# untitled.net
KiCad netlist of a schematic drawn in EAGLE
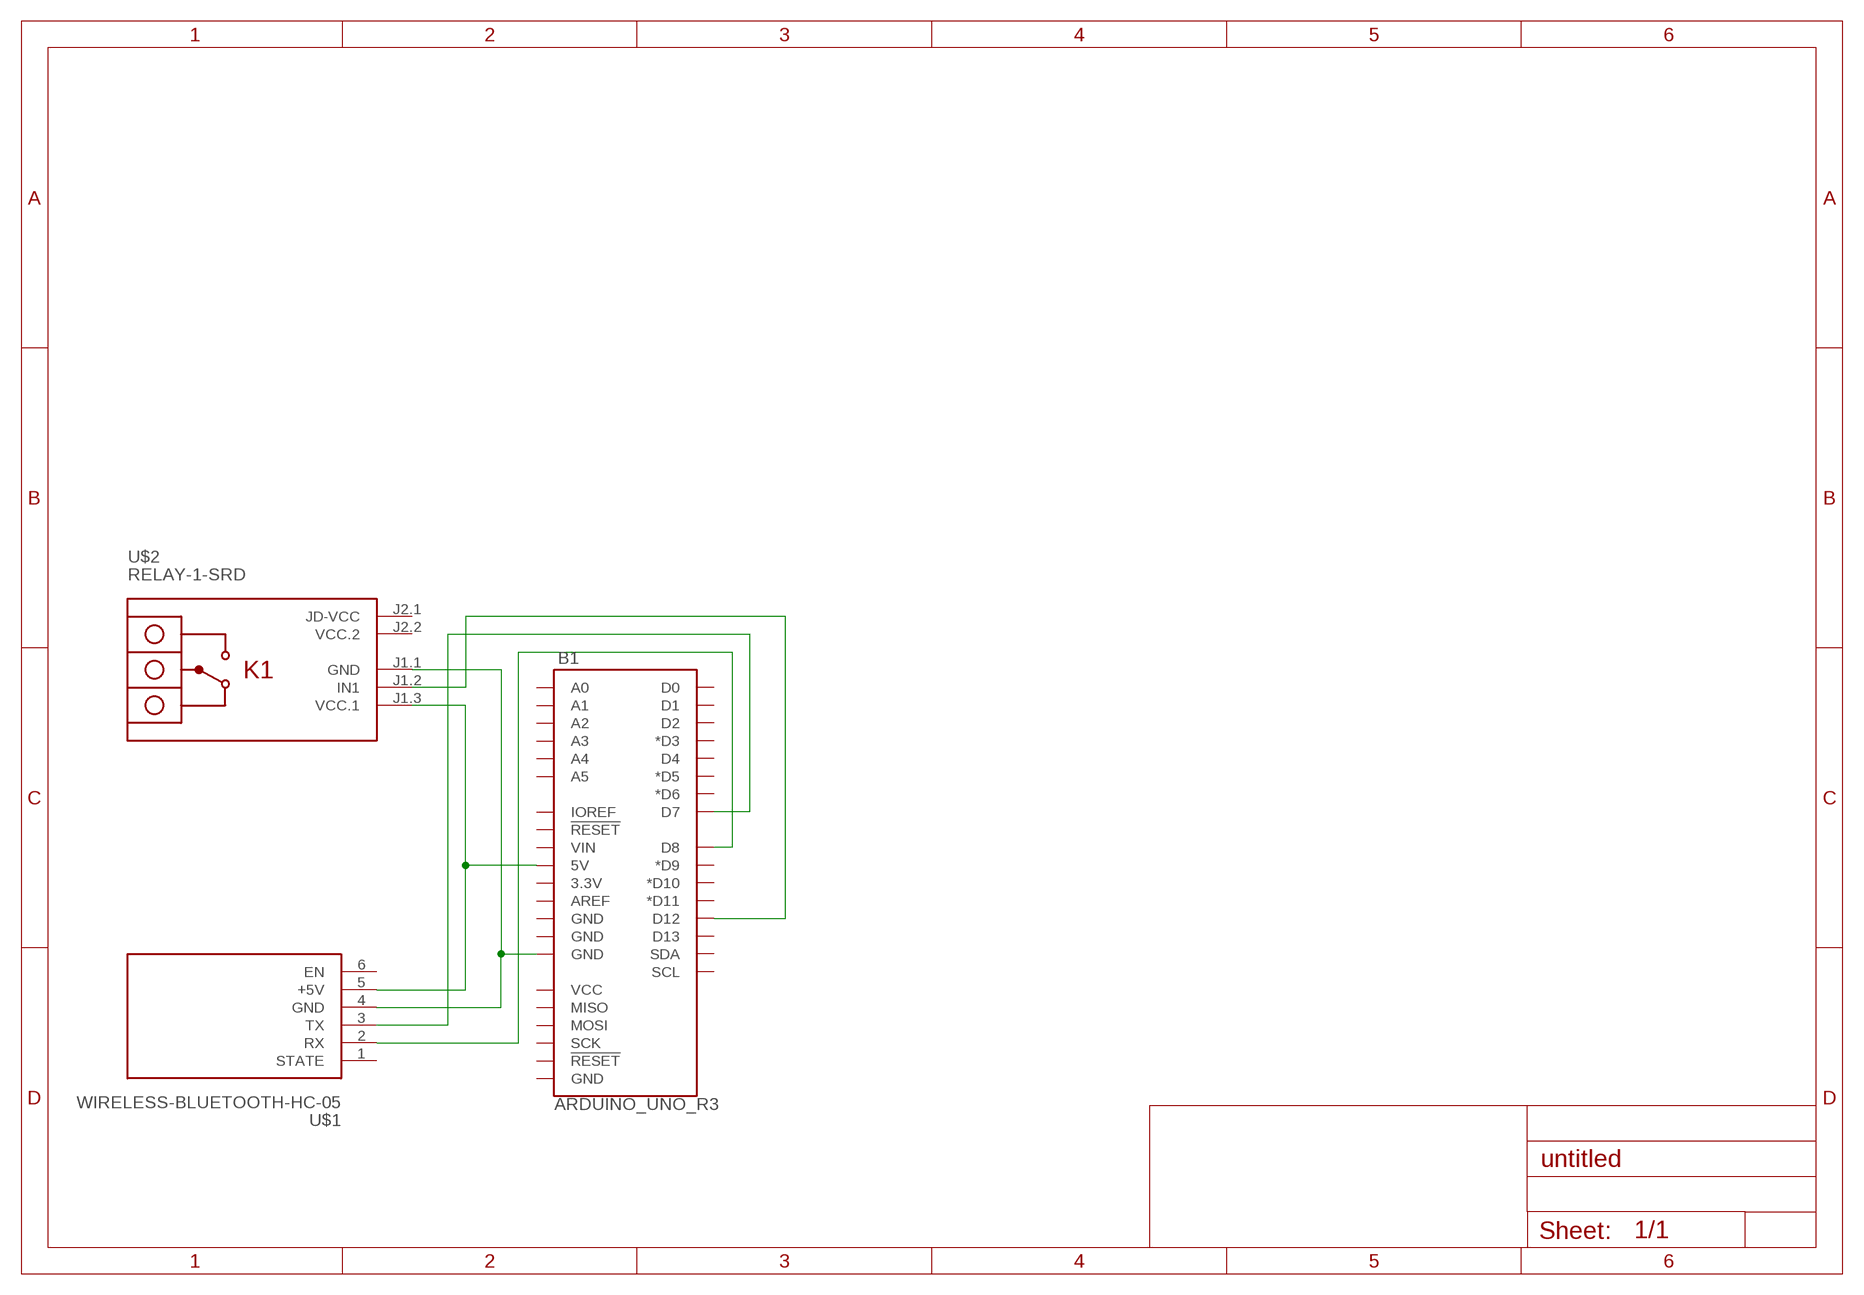
[diagram p0: schematic, sheet 1]

(export (version "E")
  (design (tool "Eeschema 10.0.6"))
  (components
    (comp (ref "B1")
      (value "ARDUINO_UNO_R3")
      (footprint "eagle-import:ARDUINO_R3")
      (libsource (lib "eagle-import") (part "ARDUINO_UNO_R3"))
    )
    (comp (ref "U$1")
      (value "WIRELESS-BLUETOOTH-HC-05")
      (footprint "eagle-import:WIRELESS-BLUETOOTH-HC-05")
      (libsource (lib "eagle-import") (part "WIRELESS-BLUETOOTH-HC-05"))
    )
    (comp (ref "U$2")
      (value "RELAY-1-SRD")
      (footprint "eagle-import:RELAY-1-SRD")
      (libsource (lib "eagle-import") (part "RELAY-1-SRD"))
    )
  )
  (nets
    (net (code "1") (name "/VCC.2") (class "Default")
      (node (ref "U$2") (pin "J2.2") (pinfunction "VCC.2_J2.2") (pintype "power_in"))
    )
    (net (code "2") (name "Net-(U$1-+5V)") (class "Default")
      (node (ref "B1") (pin "5V") (pinfunction "5V_5V") (pintype "bidirectional"))
      (node (ref "U$1") (pin "5") (pinfunction "+5V_5") (pintype "power_in"))
      (node (ref "U$2") (pin "J1.3") (pinfunction "VCC.1_J1.3") (pintype "power_in"))
    )
    (net (code "3") (name "Net-(U$1-GND)") (class "Default")
      (node (ref "B1") (pin "GND@2") (pinfunction "GND_GND@2") (pintype "bidirectional"))
      (node (ref "U$1") (pin "4") (pinfunction "GND_4") (pintype "power_in"))
      (node (ref "U$2") (pin "J1.1") (pinfunction "GND_J1.1") (pintype "power_in"))
    )
    (net (code "4") (name "Net-(U$1-RX)") (class "Default")
      (node (ref "B1") (pin "D8") (pinfunction "D8_D8") (pintype "bidirectional"))
      (node (ref "U$1") (pin "2") (pinfunction "RX_2") (pintype "bidirectional"))
    )
    (net (code "5") (name "Net-(U$1-TX)") (class "Default")
      (node (ref "B1") (pin "D7") (pinfunction "D7_D7") (pintype "bidirectional"))
      (node (ref "U$1") (pin "3") (pinfunction "TX_3") (pintype "bidirectional"))
    )
    (net (code "6") (name "Net-(U$2-IN1)") (class "Default")
      (node (ref "B1") (pin "D12") (pinfunction "D12_D12") (pintype "bidirectional"))
      (node (ref "U$2") (pin "J1.2") (pinfunction "IN1_J1.2") (pintype "bidirectional"))
    )
    (net (code "7") (name "unconnected-(B1-*D3-PadD3)") (class "Default")
      (node (ref "B1") (pin "D3") (pinfunction "*D3_D3") (pintype "bidirectional"))
    )
    (net (code "8") (name "unconnected-(B1-*D5-PadD5)") (class "Default")
      (node (ref "B1") (pin "D5") (pinfunction "*D5_D5") (pintype "bidirectional"))
    )
    (net (code "9") (name "unconnected-(B1-*D6-PadD6)") (class "Default")
      (node (ref "B1") (pin "D6") (pinfunction "*D6_D6") (pintype "bidirectional"))
    )
    (net (code "10") (name "unconnected-(B1-*D9-PadD9)") (class "Default")
      (node (ref "B1") (pin "D9") (pinfunction "*D9_D9") (pintype "bidirectional"))
    )
    (net (code "11") (name "unconnected-(B1-*D10-PadD10)") (class "Default")
      (node (ref "B1") (pin "D10") (pinfunction "*D10_D10") (pintype "bidirectional"))
    )
    (net (code "12") (name "unconnected-(B1-*D11-PadD11)") (class "Default")
      (node (ref "B1") (pin "D11") (pinfunction "*D11_D11") (pintype "bidirectional"))
    )
    (net (code "13") (name "unconnected-(B1-GND-PadGND@1)") (class "Default")
      (node (ref "B1") (pin "GND@1") (pinfunction "GND_GND@1") (pintype "bidirectional"))
    )
    (net (code "14") (name "unconnected-(B1-GND-PadGND@3)") (class "Default")
      (node (ref "B1") (pin "GND@3") (pinfunction "GND_GND@3") (pintype "bidirectional"))
    )
    (net (code "15") (name "unconnected-(B1-GND-PadGND@4)") (class "Default")
      (node (ref "B1") (pin "GND@4") (pinfunction "GND_GND@4") (pintype "bidirectional"))
    )
    (net (code "16") (name "unconnected-(B1-Pad3.3V)") (class "Default")
      (node (ref "B1") (pin "3.3V") (pinfunction "3.3V_3.3V") (pintype "bidirectional"))
    )
    (net (code "17") (name "unconnected-(B1-PadA0)") (class "Default")
      (node (ref "B1") (pin "A0") (pinfunction "A0_A0") (pintype "bidirectional"))
    )
    (net (code "18") (name "unconnected-(B1-PadA1)") (class "Default")
      (node (ref "B1") (pin "A1") (pinfunction "A1_A1") (pintype "bidirectional"))
    )
    (net (code "19") (name "unconnected-(B1-PadA2)") (class "Default")
      (node (ref "B1") (pin "A2") (pinfunction "A2_A2") (pintype "bidirectional"))
    )
    (net (code "20") (name "unconnected-(B1-PadA3)") (class "Default")
      (node (ref "B1") (pin "A3") (pinfunction "A3_A3") (pintype "bidirectional"))
    )
    (net (code "21") (name "unconnected-(B1-PadA4)") (class "Default")
      (node (ref "B1") (pin "A4") (pinfunction "A4_A4") (pintype "bidirectional"))
    )
    (net (code "22") (name "unconnected-(B1-PadA5)") (class "Default")
      (node (ref "B1") (pin "A5") (pinfunction "A5_A5") (pintype "bidirectional"))
    )
    (net (code "23") (name "unconnected-(B1-PadAREF)") (class "Default")
      (node (ref "B1") (pin "AREF") (pinfunction "AREF_AREF") (pintype "bidirectional"))
    )
    (net (code "24") (name "unconnected-(B1-PadD0)") (class "Default")
      (node (ref "B1") (pin "D0") (pinfunction "D0_D0") (pintype "bidirectional"))
    )
    (net (code "25") (name "unconnected-(B1-PadD1)") (class "Default")
      (node (ref "B1") (pin "D1") (pinfunction "D1_D1") (pintype "bidirectional"))
    )
    (net (code "26") (name "unconnected-(B1-PadD2)") (class "Default")
      (node (ref "B1") (pin "D2") (pinfunction "D2_D2") (pintype "bidirectional"))
    )
    (net (code "27") (name "unconnected-(B1-PadD4)") (class "Default")
      (node (ref "B1") (pin "D4") (pinfunction "D4_D4") (pintype "bidirectional"))
    )
    (net (code "28") (name "unconnected-(B1-PadD13)") (class "Default")
      (node (ref "B1") (pin "D13") (pinfunction "D13_D13") (pintype "bidirectional"))
    )
    (net (code "29") (name "unconnected-(B1-PadIOREF)") (class "Default")
      (node (ref "B1") (pin "IOREF") (pinfunction "IOREF_IOREF") (pintype "bidirectional"))
    )
    (net (code "30") (name "unconnected-(B1-PadMISO)") (class "Default")
      (node (ref "B1") (pin "MISO") (pinfunction "MISO_MISO") (pintype "bidirectional"))
    )
    (net (code "31") (name "unconnected-(B1-PadMOSI)") (class "Default")
      (node (ref "B1") (pin "MOSI") (pinfunction "MOSI_MOSI") (pintype "bidirectional"))
    )
    (net (code "32") (name "unconnected-(B1-PadSCK)") (class "Default")
      (node (ref "B1") (pin "SCK") (pinfunction "SCK_SCK") (pintype "bidirectional"))
    )
    (net (code "33") (name "unconnected-(B1-PadSCL)") (class "Default")
      (node (ref "B1") (pin "SCL") (pinfunction "SCL_SCL") (pintype "bidirectional"))
    )
    (net (code "34") (name "unconnected-(B1-PadSDA)") (class "Default")
      (node (ref "B1") (pin "SDA") (pinfunction "SDA_SDA") (pintype "bidirectional"))
    )
    (net (code "35") (name "unconnected-(B1-PadVCC)") (class "Default")
      (node (ref "B1") (pin "VCC") (pinfunction "VCC_VCC") (pintype "bidirectional"))
    )
    (net (code "36") (name "unconnected-(B1-PadVIN)") (class "Default")
      (node (ref "B1") (pin "VIN") (pinfunction "VIN_VIN") (pintype "bidirectional"))
    )
    (net (code "37") (name "unconnected-(B1-~{RESET}-PadRESET@1)") (class "Default")
      (node (ref "B1") (pin "RESET@1") (pinfunction "~{RESET}_RESET@1") (pintype "bidirectional"))
    )
    (net (code "38") (name "unconnected-(B1-~{RESET}-PadRESET@2)") (class "Default")
      (node (ref "B1") (pin "RESET@2") (pinfunction "~{RESET}_RESET@2") (pintype "bidirectional"))
    )
    (net (code "39") (name "unconnected-(U$1-EN-Pad6)") (class "Default")
      (node (ref "U$1") (pin "6") (pinfunction "EN_6") (pintype "bidirectional"))
    )
    (net (code "40") (name "unconnected-(U$1-STATE-Pad1)") (class "Default")
      (node (ref "U$1") (pin "1") (pinfunction "STATE_1") (pintype "bidirectional"))
    )
    (net (code "41") (name "unconnected-(U$2-JD-VCC-PadJ2.1)") (class "Default")
      (node (ref "U$2") (pin "J2.1") (pinfunction "JD-VCC_J2.1") (pintype "bidirectional"))
    )
  )
)
